# ne5555.net
KiCad netlist of a schematic drawn in Altium Designer
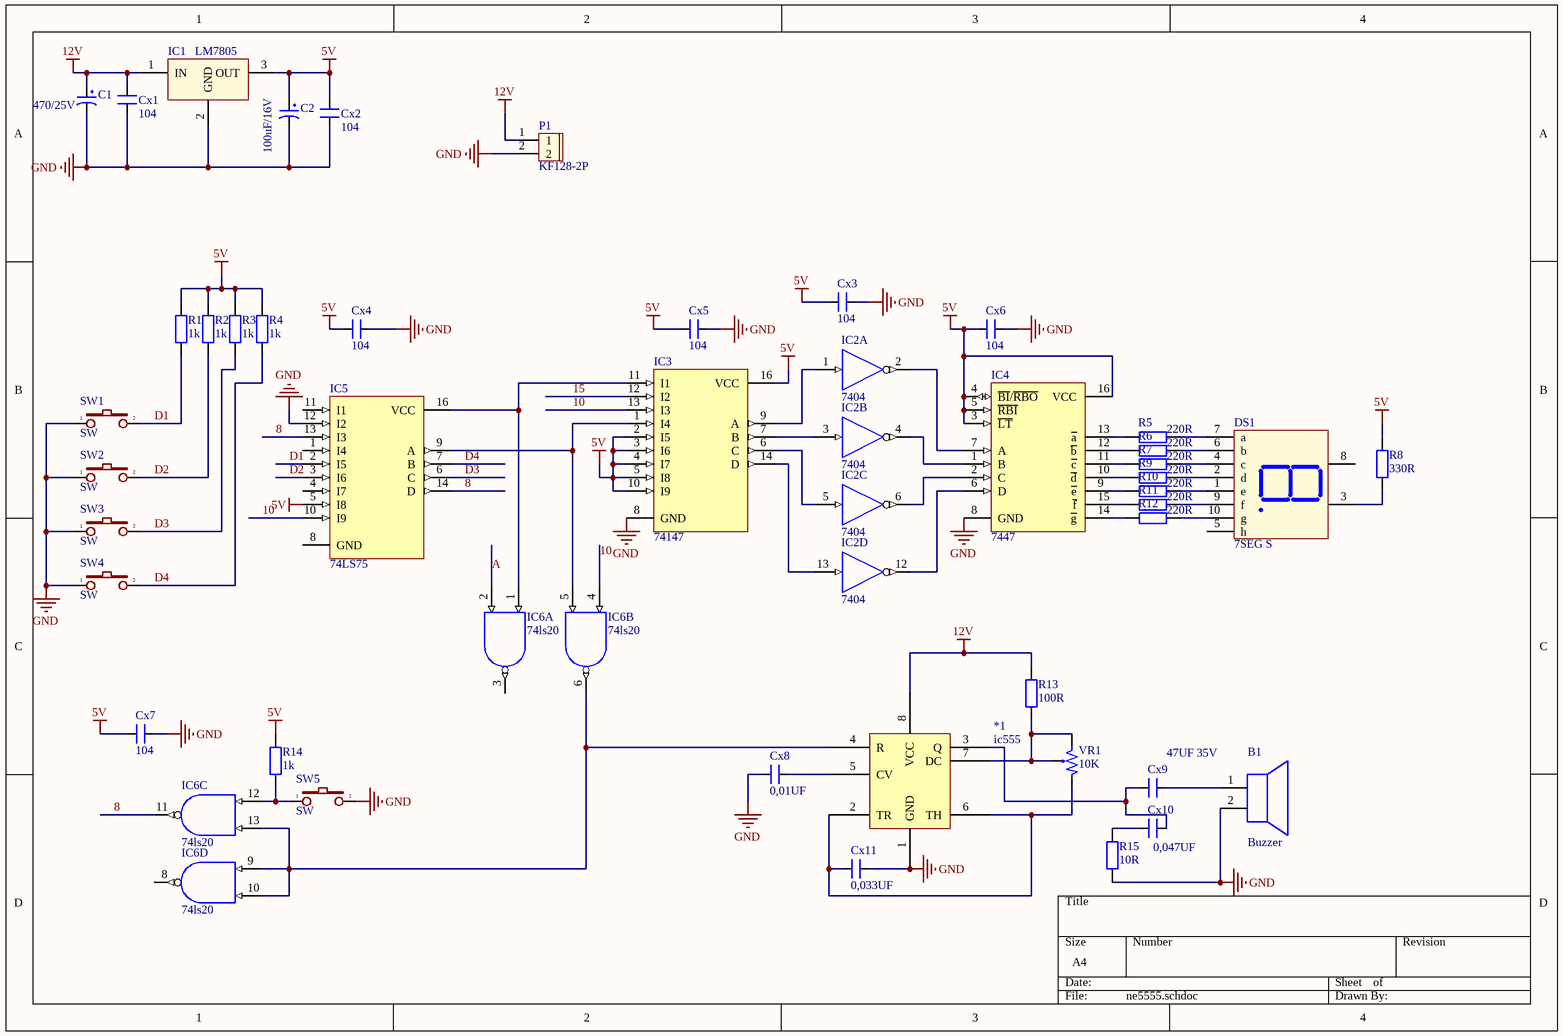
[diagram p0: ne5555.schdoc]

(export (version "E")
  (design (tool "Eeschema 10.0.6"))
  (components
    (comp (ref "*1") (value "ic555") (footprint "DIP8/W0.3") (libsource (lib "sch.hien") (part "ic555")))
    (comp (ref "B1")
      (value "Buzzer")
      (footprint "MinhTien_PcbLib:Buzzer")
      (libsource (lib "MinhTien_SCHLib") (part "Buzzer"))
    )
    (comp (ref "C1")
      (value "470/25V")
      (footprint "CP1.5/3.4")
      (description "Cap 1000uF/16V - 220uF/50V")
      (libsource (lib "TERLAB") (part "CP4"))
    )
    (comp (ref "C2")
      (value "100uF/16V")
      (footprint "CP1.5/3.4")
      (description "Cap 1000uF/16V - 220uF/50V")
      (libsource (lib "TERLAB") (part "CP4"))
    )
    (comp (ref "Cx1")
      (value "104")
      (footprint "CN1")
      (description "Cremic For Xtal 1pF => 100pF")
      (libsource (lib "TERLAB") (part "CN0"))
    )
    (comp (ref "Cx2")
      (value "104")
      (footprint "CN1")
      (description "Cremic For Xtal 1pF => 100pF")
      (libsource (lib "TERLAB") (part "CN0"))
    )
    (comp (ref "Cx3")
      (value "104")
      (footprint "CN1")
      (description "Cremic For Xtal 1pF => 100pF")
      (libsource (lib "TERLAB") (part "CN0"))
    )
    (comp (ref "Cx4")
      (value "104")
      (footprint "CN1")
      (description "Cremic For Xtal 1pF => 100pF")
      (libsource (lib "TERLAB") (part "CN0"))
    )
    (comp (ref "Cx5")
      (value "104")
      (footprint "CN1")
      (description "Cremic For Xtal 1pF => 100pF")
      (libsource (lib "TERLAB") (part "CN0"))
    )
    (comp (ref "Cx6")
      (value "104")
      (footprint "CN1")
      (description "Cremic For Xtal 1pF => 100pF")
      (libsource (lib "TERLAB") (part "CN0"))
    )
    (comp (ref "Cx7")
      (value "104")
      (footprint "CN1")
      (description "Cremic For Xtal 1pF => 100pF")
      (libsource (lib "TERLAB") (part "CN0"))
    )
    (comp (ref "Cx8")
      (value "0,01UF")
      (footprint "CN1")
      (description "Cremic For Xtal 1pF => 100pF")
      (libsource (lib "TERLAB") (part "CN0"))
    )
    (comp (ref "Cx9")
      (value "47UF 35V")
      (footprint "CN1")
      (description "Cremic For Xtal 1pF => 100pF")
      (libsource (lib "TERLAB") (part "CN0"))
    )
    (comp (ref "Cx10")
      (value "0,047UF")
      (footprint "CN1")
      (description "Cremic For Xtal 1pF => 100pF")
      (libsource (lib "TERLAB") (part "CN0"))
    )
    (comp (ref "Cx11")
      (value "0,033UF")
      (footprint "CN1")
      (description "Cremic For Xtal 1pF => 100pF")
      (libsource (lib "TERLAB") (part "CN0"))
    )
    (comp (ref "DS1")
      (value "7SEG S")
      (footprint "7SEGS")
      (description "Single 7 Seg Dipslay")
      (libsource (lib "TERLAB") (part "LED7S"))
    )
    (comp (ref "IC1")
      (value "LM7805")
      (footprint "QTO-220")
      (description "On ap +, from + 5 to + 24VDC")
      (libsource (lib "TERLAB") (part "LM78xx"))
    )
    (comp (ref "IC2")
      (value "7404")
      (footprint "DIP14/W0.3")
      (description "Hex Inverter")
      (libsource (lib "TERLAB") (part "7404"))
    )
    (comp (ref "IC3")
      (value "74147")
      (footprint "DIP16/W0.3")
      (description "10-Line to 4-Line Priority Encoder")
      (fields (field (name "COPYRIGHT BY") "VanDungEvn@Gmail.com"))
      (libsource (lib "TERLAB") (part "74147"))
    )
    (comp (ref "IC4")
      (value "7447")
      (footprint "DIP16/W0.3")
      (description "BCD to 7-Segment Decoder/Driver")
      (libsource (lib "TERLAB") (part "7447"))
    )
    (comp (ref "IC5")
      (value "74LS75")
      (footprint "DIP16/W0.3")
      (description "10-Line to 4-Line Priority Encoder")
      (fields (field (name "COPYRIGHT BY") "VanDungEvn@Gmail.com"))
      (libsource (lib "TERLAB") (part "74147"))
    )
    (comp (ref "IC6")
      (value "74ls20")
      (footprint "DIP14/W0.3")
      (description "Quad 2-Input NAND Gate")
      (fields (field (name "COPYRIGHT BY") "VanDungEvn@Gmail.com"))
      (libsource (lib "TERLAB") (part "7400"))
    )
    (comp (ref "P1")
      (value "KF128-2P")
      (footprint "con 2 kf128")
      (description "Cắm")
      (libsource (lib "SCH Chuan") (part "Con 2 kf128"))
    )
    (comp (ref "R1")
      (value "1k")
      (footprint "R1/4W")
      (description "Resistor 1/4W")
      (libsource (lib "TERLAB") (part "R1/4W"))
    )
    (comp (ref "R2")
      (value "1k")
      (footprint "R1/4W")
      (description "Resistor 1/4W")
      (libsource (lib "TERLAB") (part "R1/4W"))
    )
    (comp (ref "R3")
      (value "1k")
      (footprint "R1/4W")
      (description "Resistor 1/4W")
      (libsource (lib "TERLAB") (part "R1/4W"))
    )
    (comp (ref "R4")
      (value "1k")
      (footprint "R1/4W")
      (description "Resistor 1/4W")
      (libsource (lib "TERLAB") (part "R1/4W"))
    )
    (comp (ref "R5")
      (value "220R")
      (footprint "R1/4W")
      (description "Resistor 1/4W")
      (libsource (lib "TERLAB") (part "R1/4W"))
    )
    (comp (ref "R6")
      (value "220R")
      (footprint "R1/4W")
      (description "Resistor 1/4W")
      (libsource (lib "TERLAB") (part "R1/4W"))
    )
    (comp (ref "R7")
      (value "220R")
      (footprint "R1/4W")
      (description "Resistor 1/4W")
      (libsource (lib "TERLAB") (part "R1/4W"))
    )
    (comp (ref "R8")
      (value "330R")
      (footprint "R1/4W")
      (description "Resistor 1/4W")
      (libsource (lib "TERLAB") (part "R1/4W"))
    )
    (comp (ref "R9")
      (value "220R")
      (footprint "R1/4W")
      (description "Resistor 1/4W")
      (libsource (lib "TERLAB") (part "R1/4W"))
    )
    (comp (ref "R10")
      (value "220R")
      (footprint "R1/4W")
      (description "Resistor 1/4W")
      (libsource (lib "TERLAB") (part "R1/4W"))
    )
    (comp (ref "R11")
      (value "220R")
      (footprint "R1/4W")
      (description "Resistor 1/4W")
      (libsource (lib "TERLAB") (part "R1/4W"))
    )
    (comp (ref "R12")
      (value "220R")
      (footprint "R1/4W")
      (description "Resistor 1/4W")
      (libsource (lib "TERLAB") (part "R1/4W"))
    )
    (comp (ref "R13")
      (value "100R")
      (footprint "R1/4W")
      (description "Resistor 1/4W")
      (libsource (lib "TERLAB") (part "R1/4W"))
    )
    (comp (ref "R14")
      (value "1k")
      (footprint "R1/4W")
      (description "Resistor 1/4W")
      (libsource (lib "TERLAB") (part "R1/4W"))
    )
    (comp (ref "R15")
      (value "10R")
      (footprint "R1/4W")
      (description "Resistor 1/4W")
      (libsource (lib "TERLAB") (part "R1/4W"))
    )
    (comp (ref "SW1")
      (value "SW")
      (footprint "SW2")
      (description "Switch button 2 pin")
      (libsource (lib "TERLAB") (part "SW2"))
    )
    (comp (ref "SW2")
      (value "SW")
      (footprint "SW2")
      (description "Switch button 2 pin")
      (libsource (lib "TERLAB") (part "SW2"))
    )
    (comp (ref "SW3")
      (value "SW")
      (footprint "SW2")
      (description "Switch button 2 pin")
      (libsource (lib "TERLAB") (part "SW2"))
    )
    (comp (ref "SW4")
      (value "SW")
      (footprint "SW2")
      (description "Switch button 2 pin")
      (libsource (lib "TERLAB") (part "SW2"))
    )
    (comp (ref "SW5")
      (value "SW")
      (footprint "SW2")
      (description "Switch button 2 pin")
      (libsource (lib "TERLAB") (part "SW2"))
    )
    (comp (ref "VR1")
      (value "10K")
      (footprint "VR1")
      (description "Var Resistor")
      (libsource (lib "TERLAB") (part "VR1"))
    )
  )
  (nets
    (net (code "1") (name "/8") (class "Default")
      (node (ref "IC5") (pin "13") (pinfunction "I3_13") (pintype "input"))
      (node (ref "IC5") (pin "14") (pinfunction "D_14") (pintype "output"))
      (node (ref "IC6") (pin "11") (pinfunction "~{O}_11") (pintype "output"))
    )
    (net (code "2") (name "/10") (class "Default")
      (node (ref "IC3") (pin "13") (pinfunction "I3_13") (pintype "input"))
      (node (ref "IC5") (pin "10") (pinfunction "I9_10") (pintype "input"))
      (node (ref "IC6") (pin "4") (pinfunction "A_4") (pintype "input"))
    )
    (net (code "3") (name "/15") (class "Default")
      (node (ref "IC3") (pin "12") (pinfunction "I2_12") (pintype "input"))
    )
    (net (code "4") (name "/A") (class "Default")
      (node (ref "IC6") (pin "2") (pinfunction "B_2") (pintype "input"))
    )
    (net (code "5") (name "/D1") (class "Default")
      (node (ref "IC5") (pin "2") (pinfunction "I5_2") (pintype "input"))
      (node (ref "R1") (pin "1") (pinfunction "1_1") (pintype "passive"))
      (node (ref "SW1") (pin "2") (pinfunction "2_2") (pintype "passive"))
    )
    (net (code "6") (name "/D2") (class "Default")
      (node (ref "IC5") (pin "3") (pinfunction "I6_3") (pintype "input"))
      (node (ref "R2") (pin "1") (pinfunction "1_1") (pintype "passive"))
      (node (ref "SW2") (pin "2") (pinfunction "2_2") (pintype "passive"))
    )
    (net (code "7") (name "/D3") (class "Default")
      (node (ref "IC5") (pin "6") (pinfunction "C_6") (pintype "output"))
      (node (ref "R3") (pin "1") (pinfunction "1_1") (pintype "passive"))
      (node (ref "SW3") (pin "2") (pinfunction "2_2") (pintype "passive"))
    )
    (net (code "8") (name "/D4") (class "Default")
      (node (ref "IC5") (pin "7") (pinfunction "B_7") (pintype "output"))
      (node (ref "R4") (pin "1") (pinfunction "1_1") (pintype "passive"))
      (node (ref "SW4") (pin "2") (pinfunction "2_2") (pintype "passive"))
    )
    (net (code "9") (name "5V") (class "Default")
      (node (ref "C2") (pin "1") (pinfunction "1_1") (pintype "passive"))
      (node (ref "Cx2") (pin "2") (pinfunction "2_2") (pintype "passive"))
      (node (ref "Cx3") (pin "2") (pinfunction "2_2") (pintype "passive"))
      (node (ref "Cx4") (pin "2") (pinfunction "2_2") (pintype "passive"))
      (node (ref "Cx5") (pin "2") (pinfunction "2_2") (pintype "passive"))
      (node (ref "Cx6") (pin "2") (pinfunction "2_2") (pintype "passive"))
      (node (ref "Cx7") (pin "2") (pinfunction "2_2") (pintype "passive"))
      (node (ref "IC1") (pin "3") (pinfunction "OUT_3") (pintype "passive"))
      (node (ref "IC3") (pin "10") (pinfunction "I9_10") (pintype "input"))
      (node (ref "IC3") (pin "16") (pinfunction "VCC_16") (pintype "power_in"))
      (node (ref "IC3") (pin "2") (pinfunction "I5_2") (pintype "input"))
      (node (ref "IC3") (pin "3") (pinfunction "I6_3") (pintype "input"))
      (node (ref "IC3") (pin "4") (pinfunction "I7_4") (pintype "input"))
      (node (ref "IC3") (pin "5") (pinfunction "I8_5") (pintype "input"))
      (node (ref "IC4") (pin "16") (pinfunction "VCC_16") (pintype "power_in"))
      (node (ref "IC4") (pin "3") (pinfunction "~{LT}_3") (pintype "input"))
      (node (ref "IC4") (pin "4") (pinfunction "~{BI}/~{RBO}_4") (pintype "bidirectional"))
      (node (ref "IC4") (pin "5") (pinfunction "~{RBI}_5") (pintype "input"))
      (node (ref "IC5") (pin "5") (pinfunction "I8_5") (pintype "input"))
      (node (ref "R1") (pin "2") (pinfunction "2_2") (pintype "passive"))
      (node (ref "R14") (pin "2") (pinfunction "2_2") (pintype "passive"))
      (node (ref "R2") (pin "2") (pinfunction "2_2") (pintype "passive"))
      (node (ref "R3") (pin "2") (pinfunction "2_2") (pintype "passive"))
      (node (ref "R4") (pin "2") (pinfunction "2_2") (pintype "passive"))
      (node (ref "R8") (pin "2") (pinfunction "2_2") (pintype "passive"))
    )
    (net (code "10") (name "12V") (class "Default")
      (node (ref "*1") (pin "8") (pinfunction "VCC_8") (pintype "passive"))
      (node (ref "C1") (pin "1") (pinfunction "1_1") (pintype "passive"))
      (node (ref "Cx1") (pin "2") (pinfunction "2_2") (pintype "passive"))
      (node (ref "IC1") (pin "1") (pinfunction "IN_1") (pintype "passive"))
      (node (ref "P1") (pin "1") (pinfunction "1_1") (pintype "passive"))
      (node (ref "R13") (pin "2") (pinfunction "2_2") (pintype "passive"))
    )
    (net (code "11") (name "GND") (class "Default")
      (node (ref "*1") (pin "1") (pinfunction "GND_1") (pintype "passive"))
      (node (ref "B1") (pin "2") (pinfunction "-_2") (pintype "passive"))
      (node (ref "C1") (pin "2") (pinfunction "2_2") (pintype "passive"))
      (node (ref "C2") (pin "2") (pinfunction "2_2") (pintype "passive"))
      (node (ref "Cx1") (pin "1") (pinfunction "1_1") (pintype "passive"))
      (node (ref "Cx11") (pin "1") (pinfunction "1_1") (pintype "passive"))
      (node (ref "Cx2") (pin "1") (pinfunction "1_1") (pintype "passive"))
      (node (ref "Cx3") (pin "1") (pinfunction "1_1") (pintype "passive"))
      (node (ref "Cx4") (pin "1") (pinfunction "1_1") (pintype "passive"))
      (node (ref "Cx5") (pin "1") (pinfunction "1_1") (pintype "passive"))
      (node (ref "Cx6") (pin "1") (pinfunction "1_1") (pintype "passive"))
      (node (ref "Cx7") (pin "1") (pinfunction "1_1") (pintype "passive"))
      (node (ref "Cx8") (pin "2") (pinfunction "2_2") (pintype "passive"))
      (node (ref "IC1") (pin "2") (pinfunction "GND_2") (pintype "passive"))
      (node (ref "IC2") (pin "7") (pinfunction "GND_7") (pintype "power_in"))
      (node (ref "IC3") (pin "8") (pinfunction "GND_8") (pintype "power_in"))
      (node (ref "IC4") (pin "8") (pinfunction "GND_8") (pintype "power_in"))
      (node (ref "IC5") (pin "12") (pinfunction "I2_12") (pintype "input"))
      (node (ref "IC6") (pin "7") (pinfunction "GND_7") (pintype "power_in"))
      (node (ref "P1") (pin "2") (pinfunction "2_2") (pintype "passive"))
      (node (ref "R15") (pin "1") (pinfunction "1_1") (pintype "passive"))
      (node (ref "SW1") (pin "1") (pinfunction "1_1") (pintype "passive"))
      (node (ref "SW2") (pin "1") (pinfunction "1_1") (pintype "passive"))
      (node (ref "SW3") (pin "1") (pinfunction "1_1") (pintype "passive"))
      (node (ref "SW4") (pin "1") (pinfunction "1_1") (pintype "passive"))
      (node (ref "SW5") (pin "2") (pinfunction "2_2") (pintype "passive"))
    )
    (net (code "12") (name "Net-(*1-CV)") (class "Default")
      (node (ref "*1") (pin "5") (pinfunction "CV_5") (pintype "passive"))
      (node (ref "Cx8") (pin "1") (pinfunction "1_1") (pintype "passive"))
    )
    (net (code "13") (name "Net-(*1-DC)") (class "Default")
      (node (ref "*1") (pin "7") (pinfunction "DC_7") (pintype "passive"))
      (node (ref "R13") (pin "1") (pinfunction "1_1") (pintype "passive"))
      (node (ref "VR1") (pin "2") (pinfunction "2_2") (pintype "passive"))
      (node (ref "VR1") (pin "3") (pinfunction "3_3") (pintype "passive"))
    )
    (net (code "14") (name "Net-(*1-Q)") (class "Default")
      (node (ref "*1") (pin "3") (pinfunction "Q_3") (pintype "passive"))
      (node (ref "Cx10") (pin "2") (pinfunction "2_2") (pintype "passive"))
      (node (ref "Cx9") (pin "1") (pinfunction "1_1") (pintype "passive"))
    )
    (net (code "15") (name "Net-(*1-R)") (class "Default")
      (node (ref "*1") (pin "4") (pinfunction "R_4") (pintype "passive"))
      (node (ref "IC6") (pin "10") (pinfunction "A_10") (pintype "input"))
      (node (ref "IC6") (pin "13") (pinfunction "A_13") (pintype "input"))
      (node (ref "IC6") (pin "6") (pinfunction "~{O}_6") (pintype "output"))
      (node (ref "IC6") (pin "9") (pinfunction "B_9") (pintype "input"))
    )
    (net (code "16") (name "Net-(*1-TH)") (class "Default")
      (node (ref "*1") (pin "2") (pinfunction "TR_2") (pintype "passive"))
      (node (ref "*1") (pin "6") (pinfunction "TH_6") (pintype "passive"))
      (node (ref "Cx11") (pin "2") (pinfunction "2_2") (pintype "passive"))
      (node (ref "VR1") (pin "1") (pinfunction "1_1") (pintype "passive"))
    )
    (net (code "17") (name "Net-(B1-+)") (class "Default")
      (node (ref "B1") (pin "1") (pinfunction "+_1") (pintype "passive"))
      (node (ref "Cx9") (pin "2") (pinfunction "2_2") (pintype "passive"))
    )
    (net (code "18") (name "Net-(Cx10-Pad1)") (class "Default")
      (node (ref "Cx10") (pin "1") (pinfunction "1_1") (pintype "passive"))
      (node (ref "R15") (pin "2") (pinfunction "2_2") (pintype "passive"))
    )
    (net (code "19") (name "Net-(DS1-Vcc-Pad3)") (class "Default")
      (node (ref "DS1") (pin "3") (pinfunction "Vcc_3") (pintype "passive"))
      (node (ref "R8") (pin "1") (pinfunction "1_1") (pintype "passive"))
    )
    (net (code "20") (name "Net-(DS1-a)") (class "Default")
      (node (ref "DS1") (pin "7") (pinfunction "a_7") (pintype "passive"))
      (node (ref "R5") (pin "2") (pinfunction "2_2") (pintype "passive"))
    )
    (net (code "21") (name "Net-(DS1-b)") (class "Default")
      (node (ref "DS1") (pin "6") (pinfunction "b_6") (pintype "passive"))
      (node (ref "R6") (pin "2") (pinfunction "2_2") (pintype "passive"))
    )
    (net (code "22") (name "Net-(DS1-c)") (class "Default")
      (node (ref "DS1") (pin "4") (pinfunction "c_4") (pintype "passive"))
      (node (ref "R7") (pin "2") (pinfunction "2_2") (pintype "passive"))
    )
    (net (code "23") (name "Net-(DS1-d)") (class "Default")
      (node (ref "DS1") (pin "2") (pinfunction "d_2") (pintype "passive"))
      (node (ref "R9") (pin "2") (pinfunction "2_2") (pintype "passive"))
    )
    (net (code "24") (name "Net-(DS1-e)") (class "Default")
      (node (ref "DS1") (pin "1") (pinfunction "e_1") (pintype "passive"))
      (node (ref "R10") (pin "2") (pinfunction "2_2") (pintype "passive"))
    )
    (net (code "25") (name "Net-(DS1-f)") (class "Default")
      (node (ref "DS1") (pin "9") (pinfunction "f_9") (pintype "passive"))
      (node (ref "R11") (pin "2") (pinfunction "2_2") (pintype "passive"))
    )
    (net (code "26") (name "Net-(DS1-g)") (class "Default")
      (node (ref "DS1") (pin "10") (pinfunction "g_10") (pintype "passive"))
      (node (ref "R12") (pin "2") (pinfunction "2_2") (pintype "passive"))
    )
    (net (code "27") (name "Net-(IC2A-A)") (class "Default")
      (node (ref "IC2") (pin "1") (pinfunction "A_1") (pintype "input"))
      (node (ref "IC3") (pin "9") (pinfunction "A_9") (pintype "output"))
    )
    (net (code "28") (name "Net-(IC2A-~{O})") (class "Default")
      (node (ref "IC2") (pin "2") (pinfunction "~{O}_2") (pintype "output"))
      (node (ref "IC4") (pin "7") (pinfunction "A_7") (pintype "input"))
    )
    (net (code "29") (name "Net-(IC2B-A)") (class "Default")
      (node (ref "IC2") (pin "3") (pinfunction "A_3") (pintype "input"))
      (node (ref "IC3") (pin "7") (pinfunction "B_7") (pintype "output"))
    )
    (net (code "30") (name "Net-(IC2B-~{O})") (class "Default")
      (node (ref "IC2") (pin "4") (pinfunction "~{O}_4") (pintype "output"))
      (node (ref "IC4") (pin "1") (pinfunction "B_1") (pintype "input"))
    )
    (net (code "31") (name "Net-(IC2C-A)") (class "Default")
      (node (ref "IC2") (pin "5") (pinfunction "A_5") (pintype "input"))
      (node (ref "IC3") (pin "6") (pinfunction "C_6") (pintype "output"))
    )
    (net (code "32") (name "Net-(IC2C-~{O})") (class "Default")
      (node (ref "IC2") (pin "6") (pinfunction "~{O}_6") (pintype "output"))
      (node (ref "IC4") (pin "2") (pinfunction "C_2") (pintype "input"))
    )
    (net (code "33") (name "Net-(IC2D-A)") (class "Default")
      (node (ref "IC2") (pin "13") (pinfunction "A_13") (pintype "input"))
      (node (ref "IC3") (pin "14") (pinfunction "D_14") (pintype "output"))
    )
    (net (code "34") (name "Net-(IC2D-~{O})") (class "Default")
      (node (ref "IC2") (pin "12") (pinfunction "~{O}_12") (pintype "output"))
      (node (ref "IC4") (pin "6") (pinfunction "D_6") (pintype "input"))
    )
    (net (code "35") (name "Net-(IC3-I1)") (class "Default")
      (node (ref "IC3") (pin "11") (pinfunction "I1_11") (pintype "input"))
      (node (ref "IC5") (pin "16") (pinfunction "VCC_16") (pintype "power_in"))
      (node (ref "IC6") (pin "1") (pinfunction "A_1") (pintype "input"))
    )
    (net (code "36") (name "Net-(IC3-I4)") (class "Default")
      (node (ref "IC3") (pin "1") (pinfunction "I4_1") (pintype "input"))
      (node (ref "IC5") (pin "9") (pinfunction "A_9") (pintype "output"))
      (node (ref "IC6") (pin "5") (pinfunction "B_5") (pintype "input"))
    )
    (net (code "37") (name "Net-(IC4-~{a})") (class "Default")
      (node (ref "IC4") (pin "13") (pinfunction "~{a}_13") (pintype "open_collector"))
      (node (ref "R5") (pin "1") (pinfunction "1_1") (pintype "passive"))
    )
    (net (code "38") (name "Net-(IC4-~{b})") (class "Default")
      (node (ref "IC4") (pin "12") (pinfunction "~{b}_12") (pintype "open_collector"))
      (node (ref "R6") (pin "1") (pinfunction "1_1") (pintype "passive"))
    )
    (net (code "39") (name "Net-(IC4-~{c})") (class "Default")
      (node (ref "IC4") (pin "11") (pinfunction "~{c}_11") (pintype "open_collector"))
      (node (ref "R7") (pin "1") (pinfunction "1_1") (pintype "passive"))
    )
    (net (code "40") (name "Net-(IC4-~{d})") (class "Default")
      (node (ref "IC4") (pin "10") (pinfunction "~{d}_10") (pintype "open_collector"))
      (node (ref "R9") (pin "1") (pinfunction "1_1") (pintype "passive"))
    )
    (net (code "41") (name "Net-(IC4-~{e})") (class "Default")
      (node (ref "IC4") (pin "9") (pinfunction "~{e}_9") (pintype "open_collector"))
      (node (ref "R10") (pin "1") (pinfunction "1_1") (pintype "passive"))
    )
    (net (code "42") (name "Net-(IC4-~{f})") (class "Default")
      (node (ref "IC4") (pin "15") (pinfunction "~{f}_15") (pintype "open_collector"))
      (node (ref "R11") (pin "1") (pinfunction "1_1") (pintype "passive"))
    )
    (net (code "43") (name "Net-(IC4-~{g})") (class "Default")
      (node (ref "IC4") (pin "14") (pinfunction "~{g}_14") (pintype "open_collector"))
      (node (ref "R12") (pin "1") (pinfunction "1_1") (pintype "passive"))
    )
    (net (code "44") (name "Net-(IC6C-B)") (class "Default")
      (node (ref "IC6") (pin "12") (pinfunction "B_12") (pintype "input"))
      (node (ref "R14") (pin "1") (pinfunction "1_1") (pintype "passive"))
      (node (ref "SW5") (pin "1") (pinfunction "1_1") (pintype "passive"))
    )
    (net (code "45") (name "VCC") (class "Default")
      (node (ref "IC2") (pin "14") (pinfunction "VCC_14") (pintype "power_in"))
      (node (ref "IC6") (pin "14") (pinfunction "VCC_14") (pintype "power_in"))
    )
    (net (code "46") (name "unconnected-(DS1-Vcc-Pad8)") (class "Default")
      (node (ref "DS1") (pin "8") (pinfunction "Vcc_8") (pintype "passive"))
    )
    (net (code "47") (name "unconnected-(DS1-h-Pad5)") (class "Default")
      (node (ref "DS1") (pin "5") (pinfunction "h_5") (pintype "passive"))
    )
    (net (code "48") (name "unconnected-(IC5-GND-Pad8)") (class "Default")
      (node (ref "IC5") (pin "8") (pinfunction "GND_8") (pintype "power_in"))
    )
    (net (code "49") (name "unconnected-(IC5-I1-Pad11)") (class "Default")
      (node (ref "IC5") (pin "11") (pinfunction "I1_11") (pintype "input"))
    )
    (net (code "50") (name "unconnected-(IC5-I4-Pad1)") (class "Default")
      (node (ref "IC5") (pin "1") (pinfunction "I4_1") (pintype "input"))
    )
    (net (code "51") (name "unconnected-(IC5-I7-Pad4)") (class "Default")
      (node (ref "IC5") (pin "4") (pinfunction "I7_4") (pintype "input"))
    )
    (net (code "52") (name "unconnected-(IC6A-~{O}-Pad3)") (class "Default")
      (node (ref "IC6") (pin "3") (pinfunction "~{O}_3") (pintype "output"))
    )
    (net (code "53") (name "unconnected-(IC6D-~{O}-Pad8)") (class "Default")
      (node (ref "IC6") (pin "8") (pinfunction "~{O}_8") (pintype "output"))
    )
  )
)
